# 24_067.net
KiCad netlist of a schematic drawn in Altium Designer
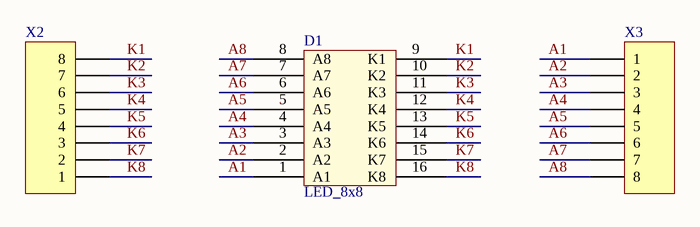
[diagram p0: 24.067.SchDoc]

(export (version "E")
  (design (tool "Eeschema 10.0.6"))
  (components
    (comp (ref "D1") (value "LED_8x8") (footprint "LED_8x8") (libsource (lib "msp_SchLib") (part "LED_8x8")))
    (comp (ref "X2")
      (value "Header 8")
      (footprint "HDR1X8")
      (description "Header, 8-Pin")
      (fields (field (name "PUBLISHER") "Altium Limited"))
      (libsource (lib "Miscellaneous Connectors") (part "Header 8"))
    )
    (comp (ref "X3")
      (value "Header 8")
      (footprint "HDR1X8")
      (description "Header, 8-Pin")
      (fields (field (name "PUBLISHER") "Altium Limited"))
      (libsource (lib "") (part "Header 8_1"))
    )
  )
  (nets
    (net (code "1") (name "/A1") (class "Default")
      (node (ref "D1") (pin "1") (pinfunction "A1_1") (pintype "passive"))
      (node (ref "X3") (pin "1") (pinfunction "1_1") (pintype "passive"))
    )
    (net (code "2") (name "/A2") (class "Default")
      (node (ref "D1") (pin "2") (pinfunction "A2_2") (pintype "passive"))
      (node (ref "X3") (pin "2") (pinfunction "2_2") (pintype "passive"))
    )
    (net (code "3") (name "/A3") (class "Default")
      (node (ref "D1") (pin "3") (pinfunction "A3_3") (pintype "passive"))
      (node (ref "X3") (pin "3") (pinfunction "3_3") (pintype "passive"))
    )
    (net (code "4") (name "/A4") (class "Default")
      (node (ref "D1") (pin "4") (pinfunction "A4_4") (pintype "passive"))
      (node (ref "X3") (pin "4") (pinfunction "4_4") (pintype "passive"))
    )
    (net (code "5") (name "/A5") (class "Default")
      (node (ref "D1") (pin "5") (pinfunction "A5_5") (pintype "passive"))
      (node (ref "X3") (pin "5") (pinfunction "5_5") (pintype "passive"))
    )
    (net (code "6") (name "/A6") (class "Default")
      (node (ref "D1") (pin "6") (pinfunction "A6_6") (pintype "passive"))
      (node (ref "X3") (pin "6") (pinfunction "6_6") (pintype "passive"))
    )
    (net (code "7") (name "/A7") (class "Default")
      (node (ref "D1") (pin "7") (pinfunction "A7_7") (pintype "passive"))
      (node (ref "X3") (pin "7") (pinfunction "7_7") (pintype "passive"))
    )
    (net (code "8") (name "/A8") (class "Default")
      (node (ref "D1") (pin "8") (pinfunction "A8_8") (pintype "passive"))
      (node (ref "X3") (pin "8") (pinfunction "8_8") (pintype "passive"))
    )
    (net (code "9") (name "/K1") (class "Default")
      (node (ref "D1") (pin "9") (pinfunction "K1_9") (pintype "passive"))
      (node (ref "X2") (pin "8") (pinfunction "8_8") (pintype "passive"))
    )
    (net (code "10") (name "/K2") (class "Default")
      (node (ref "D1") (pin "10") (pinfunction "K2_10") (pintype "passive"))
      (node (ref "X2") (pin "7") (pinfunction "7_7") (pintype "passive"))
    )
    (net (code "11") (name "/K3") (class "Default")
      (node (ref "D1") (pin "11") (pinfunction "K3_11") (pintype "passive"))
      (node (ref "X2") (pin "6") (pinfunction "6_6") (pintype "passive"))
    )
    (net (code "12") (name "/K4") (class "Default")
      (node (ref "D1") (pin "12") (pinfunction "K4_12") (pintype "passive"))
      (node (ref "X2") (pin "5") (pinfunction "5_5") (pintype "passive"))
    )
    (net (code "13") (name "/K5") (class "Default")
      (node (ref "D1") (pin "13") (pinfunction "K5_13") (pintype "passive"))
      (node (ref "X2") (pin "4") (pinfunction "4_4") (pintype "passive"))
    )
    (net (code "14") (name "/K6") (class "Default")
      (node (ref "D1") (pin "14") (pinfunction "K6_14") (pintype "passive"))
      (node (ref "X2") (pin "3") (pinfunction "3_3") (pintype "passive"))
    )
    (net (code "15") (name "/K7") (class "Default")
      (node (ref "D1") (pin "15") (pinfunction "K7_15") (pintype "passive"))
      (node (ref "X2") (pin "2") (pinfunction "2_2") (pintype "passive"))
    )
    (net (code "16") (name "/K8") (class "Default")
      (node (ref "D1") (pin "16") (pinfunction "K8_16") (pintype "passive"))
      (node (ref "X2") (pin "1") (pinfunction "1_1") (pintype "passive"))
    )
  )
)
